# IMU.net
KiCad netlist of a schematic drawn in Altium Designer
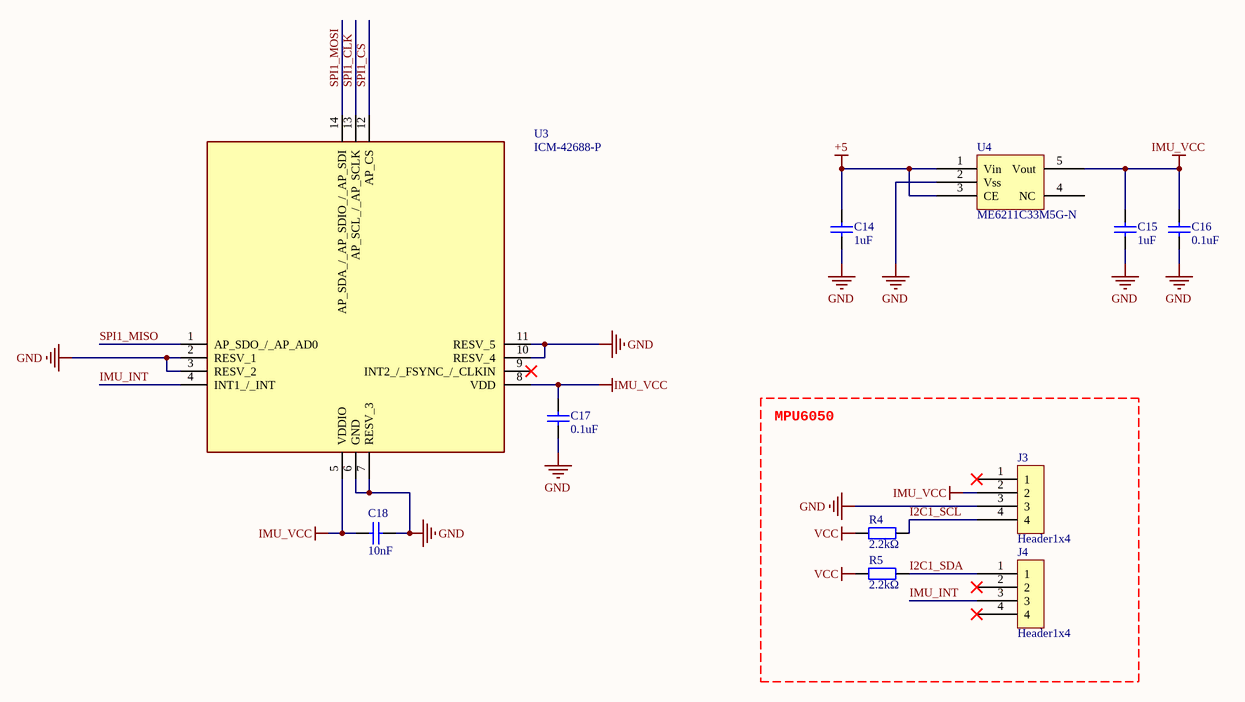
[diagram p0: IMU.SchDoc]

(export (version "E")
  (design (tool "Eeschema 10.0.6"))
  (components
    (comp (ref "C14") (value "1uF") (footprint "C0603") (libsource (lib "NetTie") (part "Capacitor")))
    (comp (ref "C15") (value "1uF") (footprint "C0603") (libsource (lib "NetTie") (part "Capacitor")))
    (comp (ref "C16") (value "0.1uF") (footprint "C0603") (libsource (lib "NetTie") (part "Capacitor")))
    (comp (ref "C17") (value "0.1uF") (footprint "C0603") (libsource (lib "NetTie") (part "Capacitor")))
    (comp (ref "C18") (value "10nF") (footprint "C0603") (libsource (lib "NetTie") (part "Capacitor")))
    (comp (ref "J3")
      (value "Header1x4")
      (footprint "Header 1x4p")
      (libsource (lib "Connectors") (part "Header1x4"))
    )
    (comp (ref "J4")
      (value "Header1x4")
      (footprint "Header 1x4p")
      (libsource (lib "Connectors") (part "Header1x4"))
    )
    (comp (ref "R4") (value "2.2kΩ") (footprint "R0603") (libsource (lib "NetTie") (part "Resistor")))
    (comp (ref "R5") (value "2.2kΩ") (footprint "R0603") (libsource (lib "NetTie") (part "Resistor")))
    (comp (ref "U3")
      (value "ICM-42688-P")
      (footprint "SamacSys:IIM42352")
      (description "Integrated Circuit")
      (fields (field (name "MOUSER PART NUMBER") "410-ICM-42688-P"))
      (libsource (lib "*") (part "ICM-42688-P"))
    )
    (comp (ref "U4")
      (value "ME6211C33M5G-N")
      (footprint "SOT-23-5")
      (description "C82942")
      (libsource (lib "PowerICs") (part "ME6211C33M5G-N"))
    )
  )
  (nets
    (net (code "1") (name "+5") (class "Default")
      (node (ref "C14") (pin "2") (pinfunction "2_2") (pintype "passive"))
      (node (ref "U4") (pin "1") (pinfunction "Vin_1") (pintype "passive"))
      (node (ref "U4") (pin "3") (pinfunction "CE_3") (pintype "passive"))
    )
    (net (code "2") (name "/I2C1_SCL") (class "Default")
      (node (ref "J3") (pin "4") (pinfunction "4_4") (pintype "passive"))
      (node (ref "R4") (pin "1") (pinfunction "1_1") (pintype "passive"))
    )
    (net (code "3") (name "/I2C1_SDA") (class "Default")
      (node (ref "J4") (pin "1") (pinfunction "1_1") (pintype "passive"))
      (node (ref "R5") (pin "1") (pinfunction "1_1") (pintype "passive"))
    )
    (net (code "4") (name "/IMU_INT") (class "Default")
      (node (ref "J4") (pin "3") (pinfunction "3_3") (pintype "passive"))
      (node (ref "U3") (pin "4") (pinfunction "INT1_/_INT_4") (pintype "passive"))
    )
    (net (code "5") (name "/SPI1_CLK") (class "Default")
      (node (ref "U3") (pin "13") (pinfunction "AP_SCL_/_AP_SCLK_13") (pintype "passive"))
    )
    (net (code "6") (name "/SPI1_CS") (class "Default")
      (node (ref "U3") (pin "12") (pinfunction "AP_CS_12") (pintype "passive"))
    )
    (net (code "7") (name "/SPI1_MISO") (class "Default")
      (node (ref "U3") (pin "1") (pinfunction "AP_SDO_/_AP_AD0_1") (pintype "passive"))
    )
    (net (code "8") (name "/SPI1_MOSI") (class "Default")
      (node (ref "U3") (pin "14") (pinfunction "AP_SDA_/_AP_SDIO_/_AP_SDI_14") (pintype "passive"))
    )
    (net (code "9") (name "GND") (class "Default")
      (node (ref "C14") (pin "1") (pinfunction "1_1") (pintype "passive"))
      (node (ref "C15") (pin "1") (pinfunction "1_1") (pintype "passive"))
      (node (ref "C16") (pin "1") (pinfunction "1_1") (pintype "passive"))
      (node (ref "C17") (pin "1") (pinfunction "1_1") (pintype "passive"))
      (node (ref "C18") (pin "1") (pinfunction "1_1") (pintype "passive"))
      (node (ref "J3") (pin "3") (pinfunction "3_3") (pintype "passive"))
      (node (ref "U3") (pin "10") (pinfunction "RESV_4_10") (pintype "passive"))
      (node (ref "U3") (pin "11") (pinfunction "RESV_5_11") (pintype "passive"))
      (node (ref "U3") (pin "2") (pinfunction "RESV_1_2") (pintype "passive"))
      (node (ref "U3") (pin "3") (pinfunction "RESV_2_3") (pintype "passive"))
      (node (ref "U3") (pin "6") (pinfunction "GND_6") (pintype "passive"))
      (node (ref "U3") (pin "7") (pinfunction "RESV_3_7") (pintype "passive"))
      (node (ref "U4") (pin "2") (pinfunction "Vss_2") (pintype "passive"))
    )
    (net (code "10") (name "IMU_VCC") (class "Default")
      (node (ref "C15") (pin "2") (pinfunction "2_2") (pintype "passive"))
      (node (ref "C16") (pin "2") (pinfunction "2_2") (pintype "passive"))
      (node (ref "C17") (pin "2") (pinfunction "2_2") (pintype "passive"))
      (node (ref "C18") (pin "2") (pinfunction "2_2") (pintype "passive"))
      (node (ref "J3") (pin "2") (pinfunction "2_2") (pintype "passive"))
      (node (ref "U3") (pin "5") (pinfunction "VDDIO_5") (pintype "passive"))
      (node (ref "U3") (pin "8") (pinfunction "VDD_8") (pintype "passive"))
      (node (ref "U4") (pin "5") (pinfunction "Vout_5") (pintype "passive"))
    )
    (net (code "11") (name "VCC") (class "Default")
      (node (ref "R4") (pin "2") (pinfunction "2_2") (pintype "passive"))
      (node (ref "R5") (pin "2") (pinfunction "2_2") (pintype "passive"))
    )
    (net (code "12") (name "unconnected-(J3-Pad1)") (class "Default")
      (node (ref "J3") (pin "1") (pinfunction "1_1") (pintype "passive+no_connect"))
    )
    (net (code "13") (name "unconnected-(J4-Pad2)") (class "Default")
      (node (ref "J4") (pin "2") (pinfunction "2_2") (pintype "passive+no_connect"))
    )
    (net (code "14") (name "unconnected-(J4-Pad4)") (class "Default")
      (node (ref "J4") (pin "4") (pinfunction "4_4") (pintype "passive+no_connect"))
    )
    (net (code "15") (name "unconnected-(U3-INT2_{slash}_FSYNC_{slash}_CLKIN-Pad9)") (class "Default")
      (node (ref "U3") (pin "9") (pinfunction "INT2_/_FSYNC_/_CLKIN_9") (pintype "passive+no_connect"))
    )
    (net (code "16") (name "unconnected-(U4-NC-Pad4)") (class "Default")
      (node (ref "U4") (pin "4") (pinfunction "NC_4") (pintype "passive"))
    )
  )
)
